# SCH_ESP32_2023-08-31.net
KiCad netlist of a schematic drawn in EasyEDA
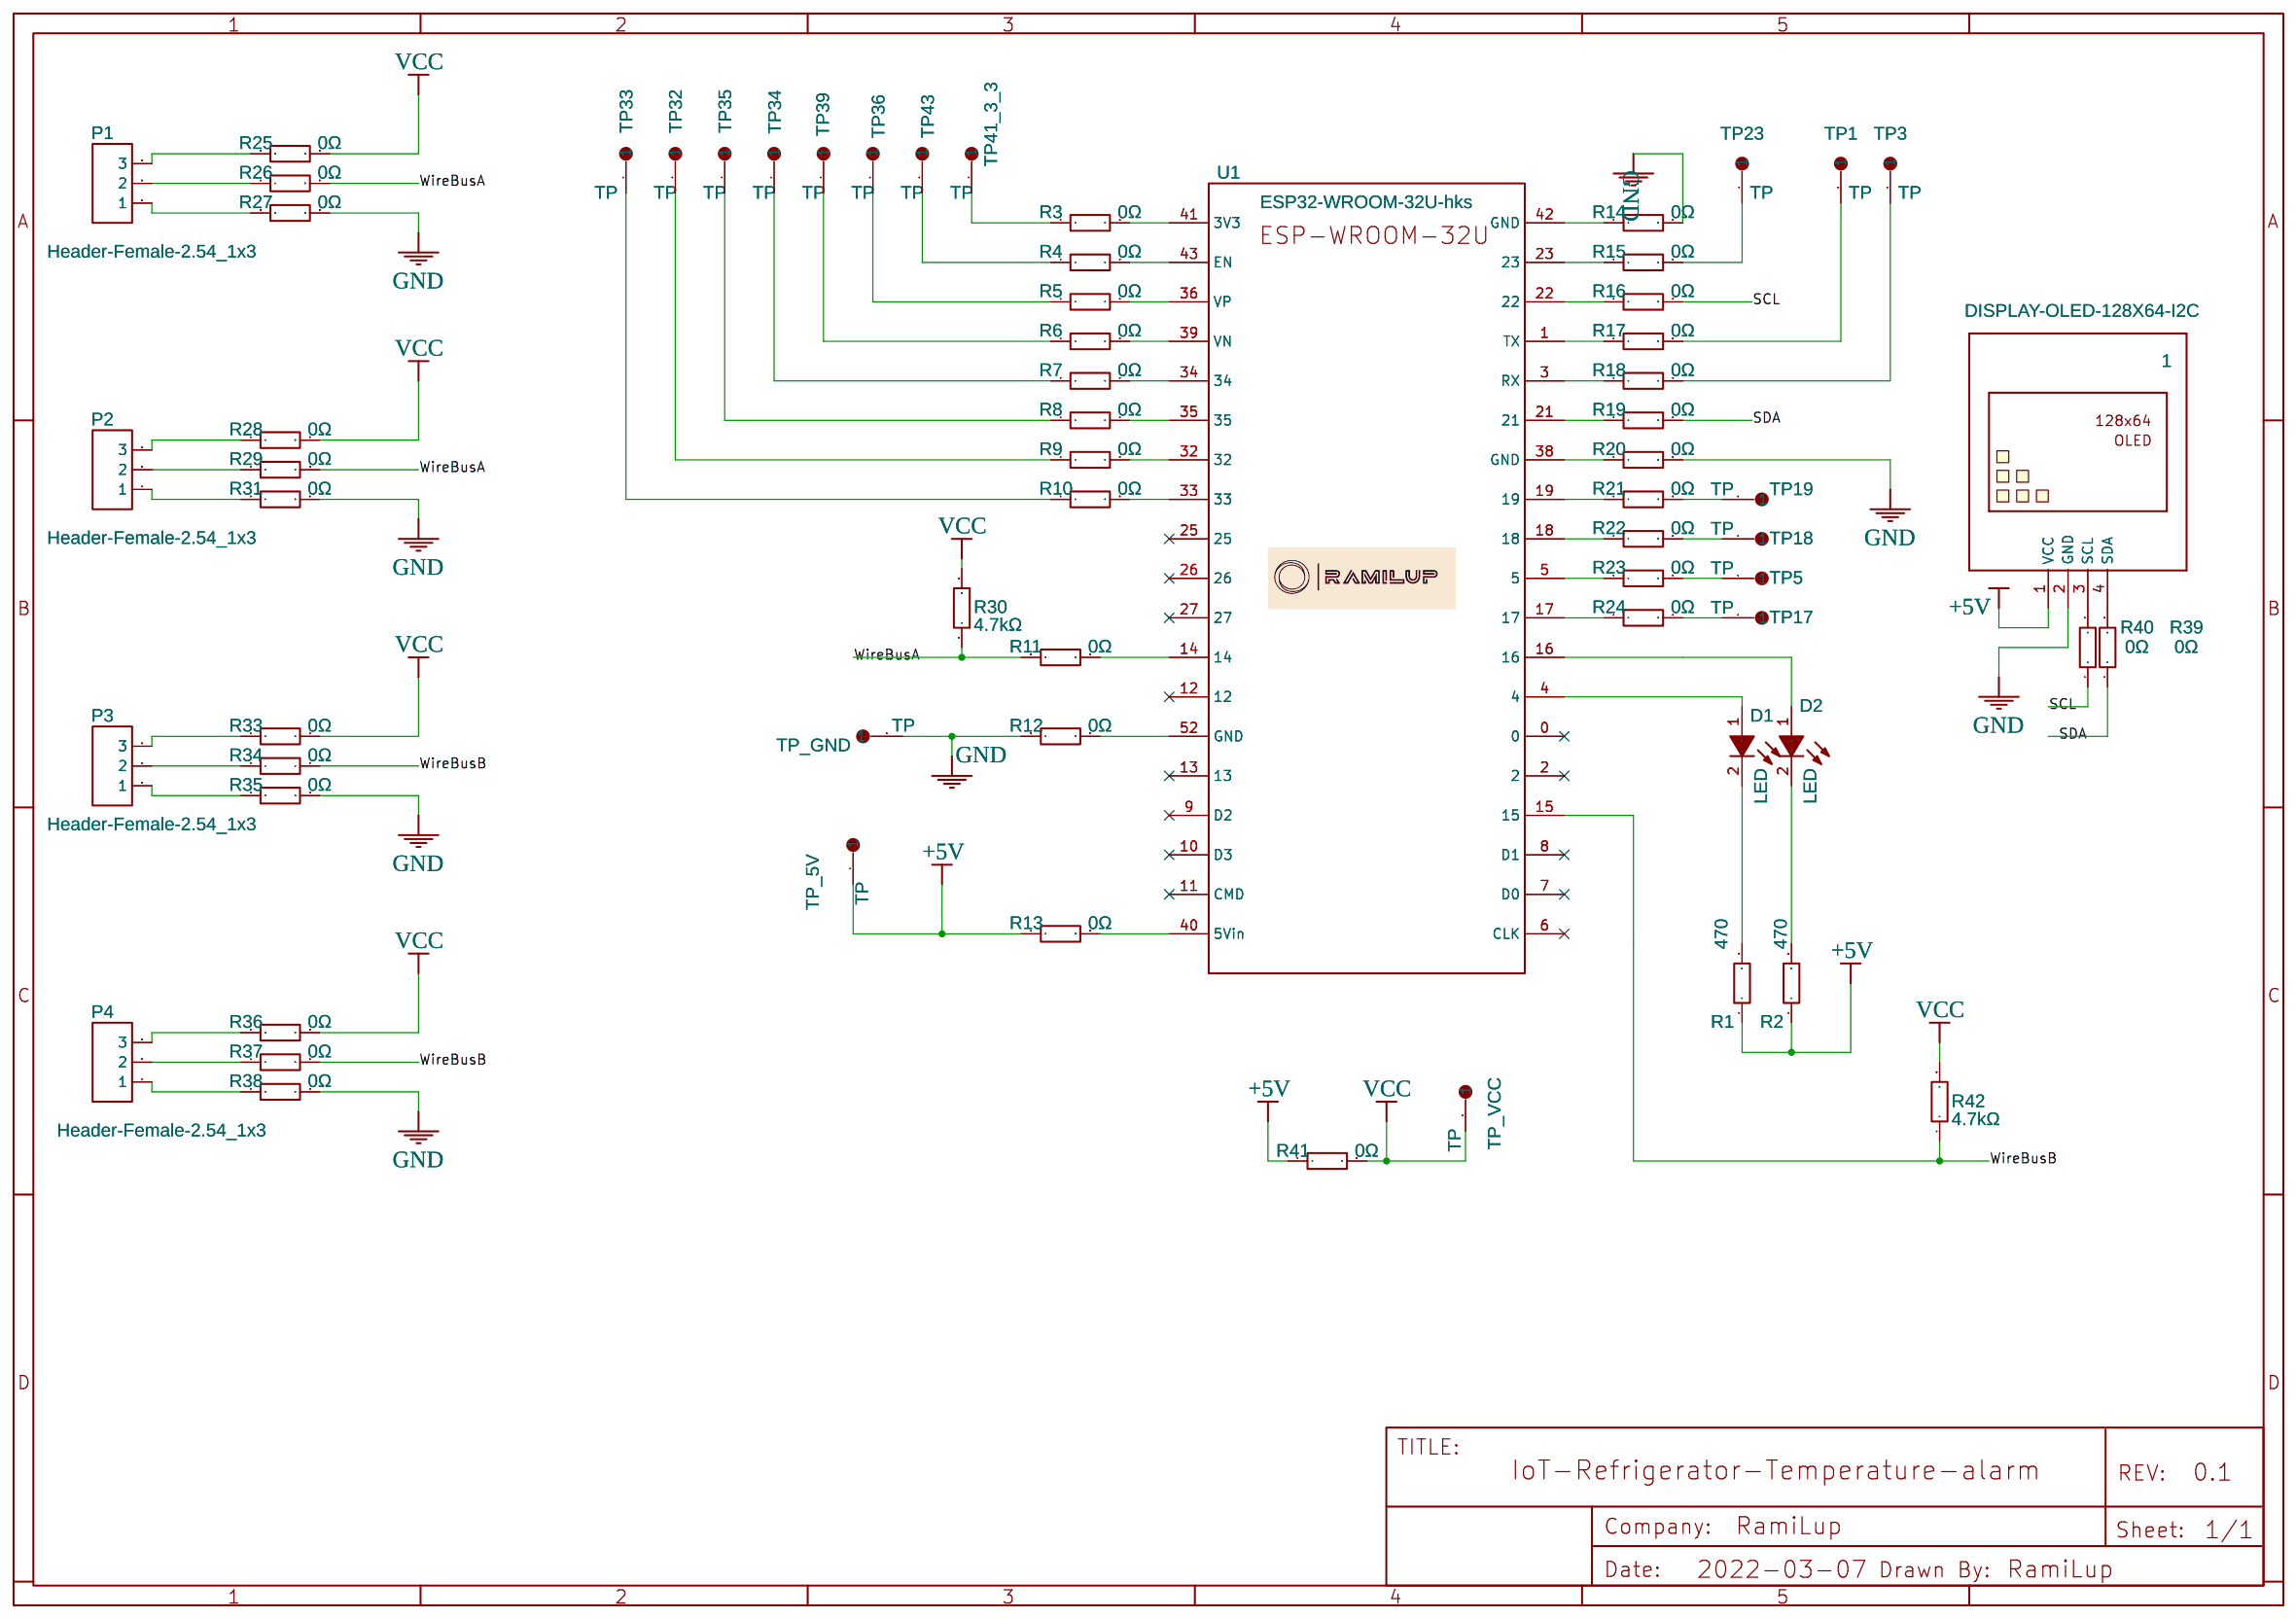
[diagram p0: schematic sheet]

(export (version "E")
  (design (tool "Eeschema 10.0.6"))
  (components
    (comp (ref "1") (value "DISPLAY-OLED-128X64-I2C") (libsource (lib "") (part "DISPLAY-OLED-128X64-I2C")))
    (comp (ref "D1")
      (value "LED")
      (fields (field (name "Manufacturer Part") "5600") (field (name "Manufacturer") "VccLite"))
      (libsource (lib "") (part "3mm Green TH LED 5600"))
    )
    (comp (ref "D2")
      (value "LED")
      (fields (field (name "Manufacturer Part") "5600") (field (name "Manufacturer") "VccLite"))
      (libsource (lib "") (part "3mm Green TH LED 5600"))
    )
    (comp (ref "P1")
      (value "Header-Female-2.54_1x3")
      (fields (field (name "Manufacturer") "Boom Precision Elec"))
      (libsource (lib "") (part "Header-Female-2.54_1x3"))
    )
    (comp (ref "P2")
      (value "Header-Female-2.54_1x3")
      (fields (field (name "Manufacturer") "Boom Precision Elec"))
      (libsource (lib "") (part "Header-Female-2.54_1x3"))
    )
    (comp (ref "P3")
      (value "Header-Female-2.54_1x3")
      (fields (field (name "Manufacturer") "Boom Precision Elec"))
      (libsource (lib "") (part "Header-Female-2.54_1x3"))
    )
    (comp (ref "P4")
      (value "Header-Female-2.54_1x3")
      (fields (field (name "Manufacturer") "Boom Precision Elec"))
      (libsource (lib "") (part "Header-Female-2.54_1x3"))
    )
    (comp (ref "R1")
      (value "470")
      (fields (field (name "Manufacturer Part") "RC2512JK-07470RL") (field (name "Manufacturer") "YAGEO"))
      (libsource (lib "") (part "RC2512JK-07470RL"))
    )
    (comp (ref "R2")
      (value "470")
      (fields (field (name "Manufacturer Part") "RC2512JK-07470RL") (field (name "Manufacturer") "YAGEO"))
      (libsource (lib "") (part "RC2512JK-07470RL"))
    )
    (comp (ref "R3")
      (value "0Ω")
      (fields
        (field (name "Manufacturer Part") "RS-06000FT")
        (field (name "Manufacturer") "Guangdong Fenghua Advanced Tech")
      )
      (libsource (lib "") (part "RS-06000FT"))
    )
    (comp (ref "R4")
      (value "0Ω")
      (fields
        (field (name "Manufacturer Part") "RS-06000FT")
        (field (name "Manufacturer") "Guangdong Fenghua Advanced Tech")
      )
      (libsource (lib "") (part "RS-06000FT"))
    )
    (comp (ref "R5")
      (value "0Ω")
      (fields
        (field (name "Manufacturer Part") "RS-06000FT")
        (field (name "Manufacturer") "Guangdong Fenghua Advanced Tech")
      )
      (libsource (lib "") (part "RS-06000FT"))
    )
    (comp (ref "R6")
      (value "0Ω")
      (fields
        (field (name "Manufacturer Part") "RS-06000FT")
        (field (name "Manufacturer") "Guangdong Fenghua Advanced Tech")
      )
      (libsource (lib "") (part "RS-06000FT"))
    )
    (comp (ref "R7")
      (value "0Ω")
      (fields
        (field (name "Manufacturer Part") "RS-06000FT")
        (field (name "Manufacturer") "Guangdong Fenghua Advanced Tech")
      )
      (libsource (lib "") (part "RS-06000FT"))
    )
    (comp (ref "R8")
      (value "0Ω")
      (fields
        (field (name "Manufacturer Part") "RS-06000FT")
        (field (name "Manufacturer") "Guangdong Fenghua Advanced Tech")
      )
      (libsource (lib "") (part "RS-06000FT"))
    )
    (comp (ref "R9")
      (value "0Ω")
      (fields
        (field (name "Manufacturer Part") "RS-06000FT")
        (field (name "Manufacturer") "Guangdong Fenghua Advanced Tech")
      )
      (libsource (lib "") (part "RS-06000FT"))
    )
    (comp (ref "R10")
      (value "0Ω")
      (fields
        (field (name "Manufacturer Part") "RS-06000FT")
        (field (name "Manufacturer") "Guangdong Fenghua Advanced Tech")
      )
      (libsource (lib "") (part "RS-06000FT"))
    )
    (comp (ref "R11")
      (value "0Ω")
      (fields
        (field (name "Manufacturer Part") "RS-06000FT")
        (field (name "Manufacturer") "Guangdong Fenghua Advanced Tech")
      )
      (libsource (lib "") (part "RS-06000FT"))
    )
    (comp (ref "R12")
      (value "0Ω")
      (fields
        (field (name "Manufacturer Part") "RS-06000FT")
        (field (name "Manufacturer") "Guangdong Fenghua Advanced Tech")
      )
      (libsource (lib "") (part "RS-06000FT"))
    )
    (comp (ref "R13")
      (value "0Ω")
      (fields
        (field (name "Manufacturer Part") "RS-06000FT")
        (field (name "Manufacturer") "Guangdong Fenghua Advanced Tech")
      )
      (libsource (lib "") (part "RS-06000FT"))
    )
    (comp (ref "R14")
      (value "0Ω")
      (fields
        (field (name "Manufacturer Part") "RS-06000FT")
        (field (name "Manufacturer") "Guangdong Fenghua Advanced Tech")
      )
      (libsource (lib "") (part "RS-06000FT"))
    )
    (comp (ref "R15")
      (value "0Ω")
      (fields
        (field (name "Manufacturer Part") "RS-06000FT")
        (field (name "Manufacturer") "Guangdong Fenghua Advanced Tech")
      )
      (libsource (lib "") (part "RS-06000FT"))
    )
    (comp (ref "R16")
      (value "0Ω")
      (fields
        (field (name "Manufacturer Part") "RS-06000FT")
        (field (name "Manufacturer") "Guangdong Fenghua Advanced Tech")
      )
      (libsource (lib "") (part "RS-06000FT"))
    )
    (comp (ref "R17")
      (value "0Ω")
      (fields
        (field (name "Manufacturer Part") "RS-06000FT")
        (field (name "Manufacturer") "Guangdong Fenghua Advanced Tech")
      )
      (libsource (lib "") (part "RS-06000FT"))
    )
    (comp (ref "R18")
      (value "0Ω")
      (fields
        (field (name "Manufacturer Part") "RS-06000FT")
        (field (name "Manufacturer") "Guangdong Fenghua Advanced Tech")
      )
      (libsource (lib "") (part "RS-06000FT"))
    )
    (comp (ref "R19")
      (value "0Ω")
      (fields
        (field (name "Manufacturer Part") "RS-06000FT")
        (field (name "Manufacturer") "Guangdong Fenghua Advanced Tech")
      )
      (libsource (lib "") (part "RS-06000FT"))
    )
    (comp (ref "R20")
      (value "0Ω")
      (fields
        (field (name "Manufacturer Part") "RS-06000FT")
        (field (name "Manufacturer") "Guangdong Fenghua Advanced Tech")
      )
      (libsource (lib "") (part "RS-06000FT"))
    )
    (comp (ref "R21")
      (value "0Ω")
      (fields
        (field (name "Manufacturer Part") "RS-06000FT")
        (field (name "Manufacturer") "Guangdong Fenghua Advanced Tech")
      )
      (libsource (lib "") (part "RS-06000FT"))
    )
    (comp (ref "R22")
      (value "0Ω")
      (fields
        (field (name "Manufacturer Part") "RS-06000FT")
        (field (name "Manufacturer") "Guangdong Fenghua Advanced Tech")
      )
      (libsource (lib "") (part "RS-06000FT"))
    )
    (comp (ref "R23")
      (value "0Ω")
      (fields
        (field (name "Manufacturer Part") "RS-06000FT")
        (field (name "Manufacturer") "Guangdong Fenghua Advanced Tech")
      )
      (libsource (lib "") (part "RS-06000FT"))
    )
    (comp (ref "R24")
      (value "0Ω")
      (fields
        (field (name "Manufacturer Part") "RS-06000FT")
        (field (name "Manufacturer") "Guangdong Fenghua Advanced Tech")
      )
      (libsource (lib "") (part "RS-06000FT"))
    )
    (comp (ref "R25")
      (value "0Ω")
      (fields
        (field (name "Manufacturer Part") "RS-06000FT")
        (field (name "Manufacturer") "Guangdong Fenghua Advanced Tech")
      )
      (libsource (lib "") (part "RS-06000FT"))
    )
    (comp (ref "R26")
      (value "0Ω")
      (fields
        (field (name "Manufacturer Part") "RS-06000FT")
        (field (name "Manufacturer") "Guangdong Fenghua Advanced Tech")
      )
      (libsource (lib "") (part "RS-06000FT"))
    )
    (comp (ref "R27")
      (value "0Ω")
      (fields
        (field (name "Manufacturer Part") "RS-06000FT")
        (field (name "Manufacturer") "Guangdong Fenghua Advanced Tech")
      )
      (libsource (lib "") (part "RS-06000FT"))
    )
    (comp (ref "R28")
      (value "0Ω")
      (fields
        (field (name "Manufacturer Part") "RS-06000FT")
        (field (name "Manufacturer") "Guangdong Fenghua Advanced Tech")
      )
      (libsource (lib "") (part "RS-06000FT"))
    )
    (comp (ref "R29")
      (value "0Ω")
      (fields
        (field (name "Manufacturer Part") "RS-06000FT")
        (field (name "Manufacturer") "Guangdong Fenghua Advanced Tech")
      )
      (libsource (lib "") (part "RS-06000FT"))
    )
    (comp (ref "R30")
      (value "4.7kΩ")
      (fields (field (name "Manufacturer Part") "RMC25124.7K1%N") (field (name "Manufacturer") "Tyohm"))
      (libsource (lib "") (part "RMC25124.7K1%N"))
    )
    (comp (ref "R31")
      (value "0Ω")
      (fields
        (field (name "Manufacturer Part") "RS-06000FT")
        (field (name "Manufacturer") "Guangdong Fenghua Advanced Tech")
      )
      (libsource (lib "") (part "RS-06000FT"))
    )
    (comp (ref "R33")
      (value "0Ω")
      (fields
        (field (name "Manufacturer Part") "RS-06000FT")
        (field (name "Manufacturer") "Guangdong Fenghua Advanced Tech")
      )
      (libsource (lib "") (part "RS-06000FT"))
    )
    (comp (ref "R34")
      (value "0Ω")
      (fields
        (field (name "Manufacturer Part") "RS-06000FT")
        (field (name "Manufacturer") "Guangdong Fenghua Advanced Tech")
      )
      (libsource (lib "") (part "RS-06000FT"))
    )
    (comp (ref "R35")
      (value "0Ω")
      (fields
        (field (name "Manufacturer Part") "RS-06000FT")
        (field (name "Manufacturer") "Guangdong Fenghua Advanced Tech")
      )
      (libsource (lib "") (part "RS-06000FT"))
    )
    (comp (ref "R36")
      (value "0Ω")
      (fields
        (field (name "Manufacturer Part") "RS-06000FT")
        (field (name "Manufacturer") "Guangdong Fenghua Advanced Tech")
      )
      (libsource (lib "") (part "RS-06000FT"))
    )
    (comp (ref "R37")
      (value "0Ω")
      (fields
        (field (name "Manufacturer Part") "RS-06000FT")
        (field (name "Manufacturer") "Guangdong Fenghua Advanced Tech")
      )
      (libsource (lib "") (part "RS-06000FT"))
    )
    (comp (ref "R38")
      (value "0Ω")
      (fields
        (field (name "Manufacturer Part") "RS-06000FT")
        (field (name "Manufacturer") "Guangdong Fenghua Advanced Tech")
      )
      (libsource (lib "") (part "RS-06000FT"))
    )
    (comp (ref "R39")
      (value "0Ω")
      (fields
        (field (name "Manufacturer Part") "RS-06000FT")
        (field (name "Manufacturer") "Guangdong Fenghua Advanced Tech")
      )
      (libsource (lib "") (part "RS-06000FT_1"))
    )
    (comp (ref "R40")
      (value "0Ω")
      (fields
        (field (name "Manufacturer Part") "RS-06000FT")
        (field (name "Manufacturer") "Guangdong Fenghua Advanced Tech")
      )
      (libsource (lib "") (part "RS-06000FT_1"))
    )
    (comp (ref "R41")
      (value "0Ω")
      (fields (field (name "Manufacturer Part") "RMC251205%N") (field (name "Manufacturer") "Tyohm"))
      (libsource (lib "") (part "RMC251205%N"))
    )
    (comp (ref "R42")
      (value "4.7kΩ")
      (fields (field (name "Manufacturer Part") "RMC25124.7K1%N") (field (name "Manufacturer") "Tyohm"))
      (libsource (lib "") (part "RMC25124.7K1%N"))
    )
    (comp (ref "TP1") (value "TP") (libsource (lib "") (part "TEST-POINT-PTH-1X1")))
    (comp (ref "TP3") (value "TP") (libsource (lib "") (part "TEST-POINT-PTH-1X1")))
    (comp (ref "TP5") (value "TP") (libsource (lib "") (part "TEST-POINT-PTH-1X1_4")))
    (comp (ref "TP17") (value "TP") (libsource (lib "") (part "TEST-POINT-PTH-1X1_4")))
    (comp (ref "TP18") (value "TP") (libsource (lib "") (part "TEST-POINT-PTH-1X1_4")))
    (comp (ref "TP19") (value "TP") (libsource (lib "") (part "TEST-POINT-PTH-1X1_4")))
    (comp (ref "TP23") (value "TP") (libsource (lib "") (part "TEST-POINT-PTH-1X1")))
    (comp (ref "TP32") (value "TP") (libsource (lib "") (part "TEST-POINT-PTH-1X1")))
    (comp (ref "TP33") (value "TP") (libsource (lib "") (part "TEST-POINT-PTH-1X1")))
    (comp (ref "TP34") (value "TP") (libsource (lib "") (part "TEST-POINT-PTH-1X1")))
    (comp (ref "TP35") (value "TP") (libsource (lib "") (part "TEST-POINT-PTH-1X1")))
    (comp (ref "TP36") (value "TP") (libsource (lib "") (part "TEST-POINT-PTH-1X1")))
    (comp (ref "TP39") (value "TP") (libsource (lib "") (part "TEST-POINT-PTH-1X1")))
    (comp (ref "TP41_3_3") (value "TP") (libsource (lib "") (part "TEST-POINT-PTH-1X1_5")))
    (comp (ref "TP43") (value "TP") (libsource (lib "") (part "TEST-POINT-PTH-1X1")))
    (comp (ref "TP_5V") (value "TP") (libsource (lib "") (part "TEST-POINT-PTH-1X1_2")))
    (comp (ref "TP_GND") (value "TP") (libsource (lib "") (part "TEST-POINT-PTH-1X1_3")))
    (comp (ref "TP_VCC") (value "TP") (libsource (lib "") (part "TEST-POINT-PTH-1X1_1")))
    (comp (ref "U1")
      (value "ESP32-WROOM-32U-hks")
      (fields
        (field (name "Manufacturer Part") "ESP32-DevKitC")
        (field (name "Manufacturer") "Espressif Systems")
      )
      (libsource (lib "") (part "ESP32-WROOM-32U-hks"))
    )
  )
  (nets
    (net (code "1") (name "+5V") (class "Default")
      (node (ref "1") (pin "1") (pinfunction "VCC_1") (pintype "passive"))
      (node (ref "R1") (pin "1") (pinfunction "1_1") (pintype "unspecified"))
      (node (ref "R13") (pin "1") (pinfunction "1_1") (pintype "unspecified"))
      (node (ref "R2") (pin "1") (pinfunction "1_1") (pintype "unspecified"))
      (node (ref "R41") (pin "1") (pinfunction "1_1") (pintype "unspecified"))
      (node (ref "TP_5V") (pin "1") (pinfunction "1_1") (pintype "unspecified"))
    )
    (net (code "2") (name "/SCL") (class "Default")
      (node (ref "R16") (pin "2") (pinfunction "2_2") (pintype "unspecified"))
      (node (ref "R40") (pin "1") (pinfunction "1_1") (pintype "unspecified"))
    )
    (net (code "3") (name "/SDA") (class "Default")
      (node (ref "R19") (pin "2") (pinfunction "2_2") (pintype "unspecified"))
      (node (ref "R39") (pin "1") (pinfunction "1_1") (pintype "unspecified"))
    )
    (net (code "4") (name "/WireBusA") (class "Default")
      (node (ref "R11") (pin "1") (pinfunction "1_1") (pintype "unspecified"))
      (node (ref "R26") (pin "2") (pinfunction "2_2") (pintype "unspecified"))
      (node (ref "R29") (pin "2") (pinfunction "2_2") (pintype "unspecified"))
      (node (ref "R30") (pin "1") (pinfunction "1_1") (pintype "unspecified"))
    )
    (net (code "5") (name "/WireBusB") (class "Default")
      (node (ref "R34") (pin "2") (pinfunction "2_2") (pintype "unspecified"))
      (node (ref "R37") (pin "2") (pinfunction "2_2") (pintype "unspecified"))
      (node (ref "R42") (pin "1") (pinfunction "1_1") (pintype "unspecified"))
      (node (ref "U1") (pin "15") (pinfunction "15_15") (pintype "unspecified"))
    )
    (net (code "6") (name "GND") (class "Default")
      (node (ref "1") (pin "2") (pinfunction "GND_2") (pintype "passive"))
      (node (ref "R12") (pin "1") (pinfunction "1_1") (pintype "unspecified"))
      (node (ref "R14") (pin "2") (pinfunction "2_2") (pintype "unspecified"))
      (node (ref "R20") (pin "2") (pinfunction "2_2") (pintype "unspecified"))
      (node (ref "R27") (pin "2") (pinfunction "2_2") (pintype "unspecified"))
      (node (ref "R31") (pin "2") (pinfunction "2_2") (pintype "unspecified"))
      (node (ref "R35") (pin "2") (pinfunction "2_2") (pintype "unspecified"))
      (node (ref "R38") (pin "2") (pinfunction "2_2") (pintype "unspecified"))
      (node (ref "TP_GND") (pin "1") (pinfunction "1_1") (pintype "unspecified"))
    )
    (net (code "7") (name "Net-(1-SCL)") (class "Default")
      (node (ref "1") (pin "3") (pinfunction "SCL_3") (pintype "bidirectional"))
      (node (ref "R40") (pin "2") (pinfunction "2_2") (pintype "unspecified"))
    )
    (net (code "8") (name "Net-(1-SDA)") (class "Default")
      (node (ref "1") (pin "4") (pinfunction "SDA_4") (pintype "bidirectional"))
      (node (ref "R39") (pin "2") (pinfunction "2_2") (pintype "unspecified"))
    )
    (net (code "9") (name "Net-(D1-A)") (class "Default")
      (node (ref "D1") (pin "1") (pinfunction "A_1") (pintype "input"))
      (node (ref "U1") (pin "4") (pinfunction "4_4") (pintype "unspecified"))
    )
    (net (code "10") (name "Net-(D1-K)") (class "Default")
      (node (ref "D1") (pin "2") (pinfunction "K_2") (pintype "input"))
      (node (ref "R1") (pin "2") (pinfunction "2_2") (pintype "unspecified"))
    )
    (net (code "11") (name "Net-(D2-A)") (class "Default")
      (node (ref "D2") (pin "1") (pinfunction "A_1") (pintype "input"))
      (node (ref "U1") (pin "16") (pinfunction "16_16") (pintype "unspecified"))
    )
    (net (code "12") (name "Net-(D2-K)") (class "Default")
      (node (ref "D2") (pin "2") (pinfunction "K_2") (pintype "input"))
      (node (ref "R2") (pin "2") (pinfunction "2_2") (pintype "unspecified"))
    )
    (net (code "13") (name "Net-(P1-Pad1)") (class "Default")
      (node (ref "P1") (pin "1") (pinfunction "1_1") (pintype "input"))
      (node (ref "R27") (pin "1") (pinfunction "1_1") (pintype "unspecified"))
    )
    (net (code "14") (name "Net-(P1-Pad2)") (class "Default")
      (node (ref "P1") (pin "2") (pinfunction "2_2") (pintype "input"))
      (node (ref "R26") (pin "1") (pinfunction "1_1") (pintype "unspecified"))
    )
    (net (code "15") (name "Net-(P1-Pad3)") (class "Default")
      (node (ref "P1") (pin "3") (pinfunction "3_3") (pintype "input"))
      (node (ref "R25") (pin "1") (pinfunction "1_1") (pintype "unspecified"))
    )
    (net (code "16") (name "Net-(P2-Pad1)") (class "Default")
      (node (ref "P2") (pin "1") (pinfunction "1_1") (pintype "input"))
      (node (ref "R31") (pin "1") (pinfunction "1_1") (pintype "unspecified"))
    )
    (net (code "17") (name "Net-(P2-Pad2)") (class "Default")
      (node (ref "P2") (pin "2") (pinfunction "2_2") (pintype "input"))
      (node (ref "R29") (pin "1") (pinfunction "1_1") (pintype "unspecified"))
    )
    (net (code "18") (name "Net-(P2-Pad3)") (class "Default")
      (node (ref "P2") (pin "3") (pinfunction "3_3") (pintype "input"))
      (node (ref "R28") (pin "1") (pinfunction "1_1") (pintype "unspecified"))
    )
    (net (code "19") (name "Net-(P3-Pad1)") (class "Default")
      (node (ref "P3") (pin "1") (pinfunction "1_1") (pintype "input"))
      (node (ref "R35") (pin "1") (pinfunction "1_1") (pintype "unspecified"))
    )
    (net (code "20") (name "Net-(P3-Pad2)") (class "Default")
      (node (ref "P3") (pin "2") (pinfunction "2_2") (pintype "input"))
      (node (ref "R34") (pin "1") (pinfunction "1_1") (pintype "unspecified"))
    )
    (net (code "21") (name "Net-(P3-Pad3)") (class "Default")
      (node (ref "P3") (pin "3") (pinfunction "3_3") (pintype "input"))
      (node (ref "R33") (pin "1") (pinfunction "1_1") (pintype "unspecified"))
    )
    (net (code "22") (name "Net-(P4-Pad1)") (class "Default")
      (node (ref "P4") (pin "1") (pinfunction "1_1") (pintype "input"))
      (node (ref "R38") (pin "1") (pinfunction "1_1") (pintype "unspecified"))
    )
    (net (code "23") (name "Net-(P4-Pad2)") (class "Default")
      (node (ref "P4") (pin "2") (pinfunction "2_2") (pintype "input"))
      (node (ref "R37") (pin "1") (pinfunction "1_1") (pintype "unspecified"))
    )
    (net (code "24") (name "Net-(P4-Pad3)") (class "Default")
      (node (ref "P4") (pin "3") (pinfunction "3_3") (pintype "input"))
      (node (ref "R36") (pin "1") (pinfunction "1_1") (pintype "unspecified"))
    )
    (net (code "25") (name "Net-(R3-Pad1)") (class "Default")
      (node (ref "R3") (pin "1") (pinfunction "1_1") (pintype "unspecified"))
      (node (ref "TP41_3_3") (pin "1") (pinfunction "1_1") (pintype "unspecified"))
    )
    (net (code "26") (name "Net-(R4-Pad1)") (class "Default")
      (node (ref "R4") (pin "1") (pinfunction "1_1") (pintype "unspecified"))
      (node (ref "TP43") (pin "1") (pinfunction "1_1") (pintype "unspecified"))
    )
    (net (code "27") (name "Net-(R5-Pad1)") (class "Default")
      (node (ref "R5") (pin "1") (pinfunction "1_1") (pintype "unspecified"))
      (node (ref "TP36") (pin "1") (pinfunction "1_1") (pintype "unspecified"))
    )
    (net (code "28") (name "Net-(R6-Pad1)") (class "Default")
      (node (ref "R6") (pin "1") (pinfunction "1_1") (pintype "unspecified"))
      (node (ref "TP39") (pin "1") (pinfunction "1_1") (pintype "unspecified"))
    )
    (net (code "29") (name "Net-(R7-Pad1)") (class "Default")
      (node (ref "R7") (pin "1") (pinfunction "1_1") (pintype "unspecified"))
      (node (ref "TP34") (pin "1") (pinfunction "1_1") (pintype "unspecified"))
    )
    (net (code "30") (name "Net-(R7-Pad2)") (class "Default")
      (node (ref "R7") (pin "2") (pinfunction "2_2") (pintype "unspecified"))
      (node (ref "U1") (pin "34") (pinfunction "34_34") (pintype "unspecified"))
    )
    (net (code "31") (name "Net-(R8-Pad1)") (class "Default")
      (node (ref "R8") (pin "1") (pinfunction "1_1") (pintype "unspecified"))
      (node (ref "TP35") (pin "1") (pinfunction "1_1") (pintype "unspecified"))
    )
    (net (code "32") (name "Net-(R8-Pad2)") (class "Default")
      (node (ref "R8") (pin "2") (pinfunction "2_2") (pintype "unspecified"))
      (node (ref "U1") (pin "35") (pinfunction "35_35") (pintype "unspecified"))
    )
    (net (code "33") (name "Net-(R9-Pad1)") (class "Default")
      (node (ref "R9") (pin "1") (pinfunction "1_1") (pintype "unspecified"))
      (node (ref "TP32") (pin "1") (pinfunction "1_1") (pintype "unspecified"))
    )
    (net (code "34") (name "Net-(R9-Pad2)") (class "Default")
      (node (ref "R9") (pin "2") (pinfunction "2_2") (pintype "unspecified"))
      (node (ref "U1") (pin "32") (pinfunction "32_32") (pintype "unspecified"))
    )
    (net (code "35") (name "Net-(R10-Pad1)") (class "Default")
      (node (ref "R10") (pin "1") (pinfunction "1_1") (pintype "unspecified"))
      (node (ref "TP33") (pin "1") (pinfunction "1_1") (pintype "unspecified"))
    )
    (net (code "36") (name "Net-(R10-Pad2)") (class "Default")
      (node (ref "R10") (pin "2") (pinfunction "2_2") (pintype "unspecified"))
      (node (ref "U1") (pin "33") (pinfunction "33_33") (pintype "unspecified"))
    )
    (net (code "37") (name "Net-(R11-Pad2)") (class "Default")
      (node (ref "R11") (pin "2") (pinfunction "2_2") (pintype "unspecified"))
      (node (ref "U1") (pin "14") (pinfunction "14_14") (pintype "unspecified"))
    )
    (net (code "38") (name "Net-(R12-Pad2)") (class "Default")
      (node (ref "R12") (pin "2") (pinfunction "2_2") (pintype "unspecified"))
      (node (ref "U1") (pin "52") (pinfunction "GND_52") (pintype "passive"))
    )
    (net (code "39") (name "Net-(R14-Pad1)") (class "Default")
      (node (ref "R14") (pin "1") (pinfunction "1_1") (pintype "unspecified"))
      (node (ref "U1") (pin "42") (pinfunction "GND_42") (pintype "passive"))
    )
    (net (code "40") (name "Net-(R15-Pad1)") (class "Default")
      (node (ref "R15") (pin "1") (pinfunction "1_1") (pintype "unspecified"))
      (node (ref "U1") (pin "23") (pinfunction "23_23") (pintype "unspecified"))
    )
    (net (code "41") (name "Net-(R15-Pad2)") (class "Default")
      (node (ref "R15") (pin "2") (pinfunction "2_2") (pintype "unspecified"))
      (node (ref "TP23") (pin "1") (pinfunction "1_1") (pintype "unspecified"))
    )
    (net (code "42") (name "Net-(R16-Pad1)") (class "Default")
      (node (ref "R16") (pin "1") (pinfunction "1_1") (pintype "unspecified"))
      (node (ref "U1") (pin "22") (pinfunction "22_22") (pintype "unspecified"))
    )
    (net (code "43") (name "Net-(R17-Pad2)") (class "Default")
      (node (ref "R17") (pin "2") (pinfunction "2_2") (pintype "unspecified"))
      (node (ref "TP1") (pin "1") (pinfunction "1_1") (pintype "unspecified"))
    )
    (net (code "44") (name "Net-(R18-Pad2)") (class "Default")
      (node (ref "R18") (pin "2") (pinfunction "2_2") (pintype "unspecified"))
      (node (ref "TP3") (pin "1") (pinfunction "1_1") (pintype "unspecified"))
    )
    (net (code "45") (name "Net-(R19-Pad1)") (class "Default")
      (node (ref "R19") (pin "1") (pinfunction "1_1") (pintype "unspecified"))
      (node (ref "U1") (pin "21") (pinfunction "21_21") (pintype "unspecified"))
    )
    (net (code "46") (name "Net-(R20-Pad1)") (class "Default")
      (node (ref "R20") (pin "1") (pinfunction "1_1") (pintype "unspecified"))
      (node (ref "U1") (pin "38") (pinfunction "GND_38") (pintype "passive"))
    )
    (net (code "47") (name "Net-(R21-Pad1)") (class "Default")
      (node (ref "R21") (pin "1") (pinfunction "1_1") (pintype "unspecified"))
      (node (ref "U1") (pin "19") (pinfunction "19_19") (pintype "unspecified"))
    )
    (net (code "48") (name "Net-(R21-Pad2)") (class "Default")
      (node (ref "R21") (pin "2") (pinfunction "2_2") (pintype "unspecified"))
      (node (ref "TP19") (pin "1") (pinfunction "1_1") (pintype "unspecified"))
    )
    (net (code "49") (name "Net-(R22-Pad1)") (class "Default")
      (node (ref "R22") (pin "1") (pinfunction "1_1") (pintype "unspecified"))
      (node (ref "U1") (pin "18") (pinfunction "18_18") (pintype "unspecified"))
    )
    (net (code "50") (name "Net-(R22-Pad2)") (class "Default")
      (node (ref "R22") (pin "2") (pinfunction "2_2") (pintype "unspecified"))
      (node (ref "TP18") (pin "1") (pinfunction "1_1") (pintype "unspecified"))
    )
    (net (code "51") (name "Net-(R23-Pad1)") (class "Default")
      (node (ref "R23") (pin "1") (pinfunction "1_1") (pintype "unspecified"))
      (node (ref "U1") (pin "5") (pinfunction "5_5") (pintype "unspecified"))
    )
    (net (code "52") (name "Net-(R23-Pad2)") (class "Default")
      (node (ref "R23") (pin "2") (pinfunction "2_2") (pintype "unspecified"))
      (node (ref "TP5") (pin "1") (pinfunction "1_1") (pintype "unspecified"))
    )
    (net (code "53") (name "Net-(R24-Pad1)") (class "Default")
      (node (ref "R24") (pin "1") (pinfunction "1_1") (pintype "unspecified"))
      (node (ref "U1") (pin "17") (pinfunction "17_17") (pintype "unspecified"))
    )
    (net (code "54") (name "Net-(R24-Pad2)") (class "Default")
      (node (ref "R24") (pin "2") (pinfunction "2_2") (pintype "unspecified"))
      (node (ref "TP17") (pin "1") (pinfunction "1_1") (pintype "unspecified"))
    )
    (net (code "55") (name "Net-(U1-3V3)") (class "Default")
      (node (ref "R3") (pin "2") (pinfunction "2_2") (pintype "unspecified"))
      (node (ref "U1") (pin "41") (pinfunction "3V3_41") (pintype "passive"))
    )
    (net (code "56") (name "Net-(U1-5Vin)") (class "Default")
      (node (ref "R13") (pin "2") (pinfunction "2_2") (pintype "unspecified"))
      (node (ref "U1") (pin "40") (pinfunction "5Vin_40") (pintype "passive"))
    )
    (net (code "57") (name "Net-(U1-EN)") (class "Default")
      (node (ref "R4") (pin "2") (pinfunction "2_2") (pintype "unspecified"))
      (node (ref "U1") (pin "43") (pinfunction "EN_43") (pintype "unspecified"))
    )
    (net (code "58") (name "Net-(U1-RX)") (class "Default")
      (node (ref "R18") (pin "1") (pinfunction "1_1") (pintype "unspecified"))
      (node (ref "U1") (pin "3") (pinfunction "RX_3") (pintype "unspecified"))
    )
    (net (code "59") (name "Net-(U1-TX)") (class "Default")
      (node (ref "R17") (pin "1") (pinfunction "1_1") (pintype "unspecified"))
      (node (ref "U1") (pin "1") (pinfunction "TX_1") (pintype "unspecified"))
    )
    (net (code "60") (name "Net-(U1-VN)") (class "Default")
      (node (ref "R6") (pin "2") (pinfunction "2_2") (pintype "unspecified"))
      (node (ref "U1") (pin "39") (pinfunction "VN_39") (pintype "unspecified"))
    )
    (net (code "61") (name "Net-(U1-VP)") (class "Default")
      (node (ref "R5") (pin "2") (pinfunction "2_2") (pintype "unspecified"))
      (node (ref "U1") (pin "36") (pinfunction "VP_36") (pintype "unspecified"))
    )
    (net (code "62") (name "VCC") (class "Default")
      (node (ref "R25") (pin "2") (pinfunction "2_2") (pintype "unspecified"))
      (node (ref "R28") (pin "2") (pinfunction "2_2") (pintype "unspecified"))
      (node (ref "R30") (pin "2") (pinfunction "2_2") (pintype "unspecified"))
      (node (ref "R33") (pin "2") (pinfunction "2_2") (pintype "unspecified"))
      (node (ref "R36") (pin "2") (pinfunction "2_2") (pintype "unspecified"))
      (node (ref "R41") (pin "2") (pinfunction "2_2") (pintype "unspecified"))
      (node (ref "R42") (pin "2") (pinfunction "2_2") (pintype "unspecified"))
      (node (ref "TP_VCC") (pin "1") (pinfunction "1_1") (pintype "unspecified"))
    )
    (net (code "63") (name "unconnected-(U1-CLK-Pad6)") (class "Default")
      (node (ref "U1") (pin "6") (pinfunction "CLK_6") (pintype "unspecified+no_connect"))
    )
    (net (code "64") (name "unconnected-(U1-CMD-Pad11)") (class "Default")
      (node (ref "U1") (pin "11") (pinfunction "CMD_11") (pintype "unspecified+no_connect"))
    )
    (net (code "65") (name "unconnected-(U1-D0-Pad7)") (class "Default")
      (node (ref "U1") (pin "7") (pinfunction "D0_7") (pintype "unspecified+no_connect"))
    )
    (net (code "66") (name "unconnected-(U1-D1-Pad8)") (class "Default")
      (node (ref "U1") (pin "8") (pinfunction "D1_8") (pintype "unspecified+no_connect"))
    )
    (net (code "67") (name "unconnected-(U1-D2-Pad9)") (class "Default")
      (node (ref "U1") (pin "9") (pinfunction "D2_9") (pintype "unspecified+no_connect"))
    )
    (net (code "68") (name "unconnected-(U1-D3-Pad10)") (class "Default")
      (node (ref "U1") (pin "10") (pinfunction "D3_10") (pintype "unspecified+no_connect"))
    )
    (net (code "69") (name "unconnected-(U1-Pad0)") (class "Default")
      (node (ref "U1") (pin "0") (pinfunction "0_0") (pintype "unspecified+no_connect"))
    )
    (net (code "70") (name "unconnected-(U1-Pad2)") (class "Default")
      (node (ref "U1") (pin "2") (pinfunction "2_2") (pintype "unspecified+no_connect"))
    )
    (net (code "71") (name "unconnected-(U1-Pad12)") (class "Default")
      (node (ref "U1") (pin "12") (pinfunction "12_12") (pintype "unspecified+no_connect"))
    )
    (net (code "72") (name "unconnected-(U1-Pad13)") (class "Default")
      (node (ref "U1") (pin "13") (pinfunction "13_13") (pintype "unspecified+no_connect"))
    )
    (net (code "73") (name "unconnected-(U1-Pad25)") (class "Default")
      (node (ref "U1") (pin "25") (pinfunction "25_25") (pintype "unspecified+no_connect"))
    )
    (net (code "74") (name "unconnected-(U1-Pad26)") (class "Default")
      (node (ref "U1") (pin "26") (pinfunction "26_26") (pintype "unspecified+no_connect"))
    )
    (net (code "75") (name "unconnected-(U1-Pad27)") (class "Default")
      (node (ref "U1") (pin "27") (pinfunction "27_27") (pintype "unspecified+no_connect"))
    )
  )
)
